# schematic.net
KiCad netlist of a schematic drawn in EasyEDA
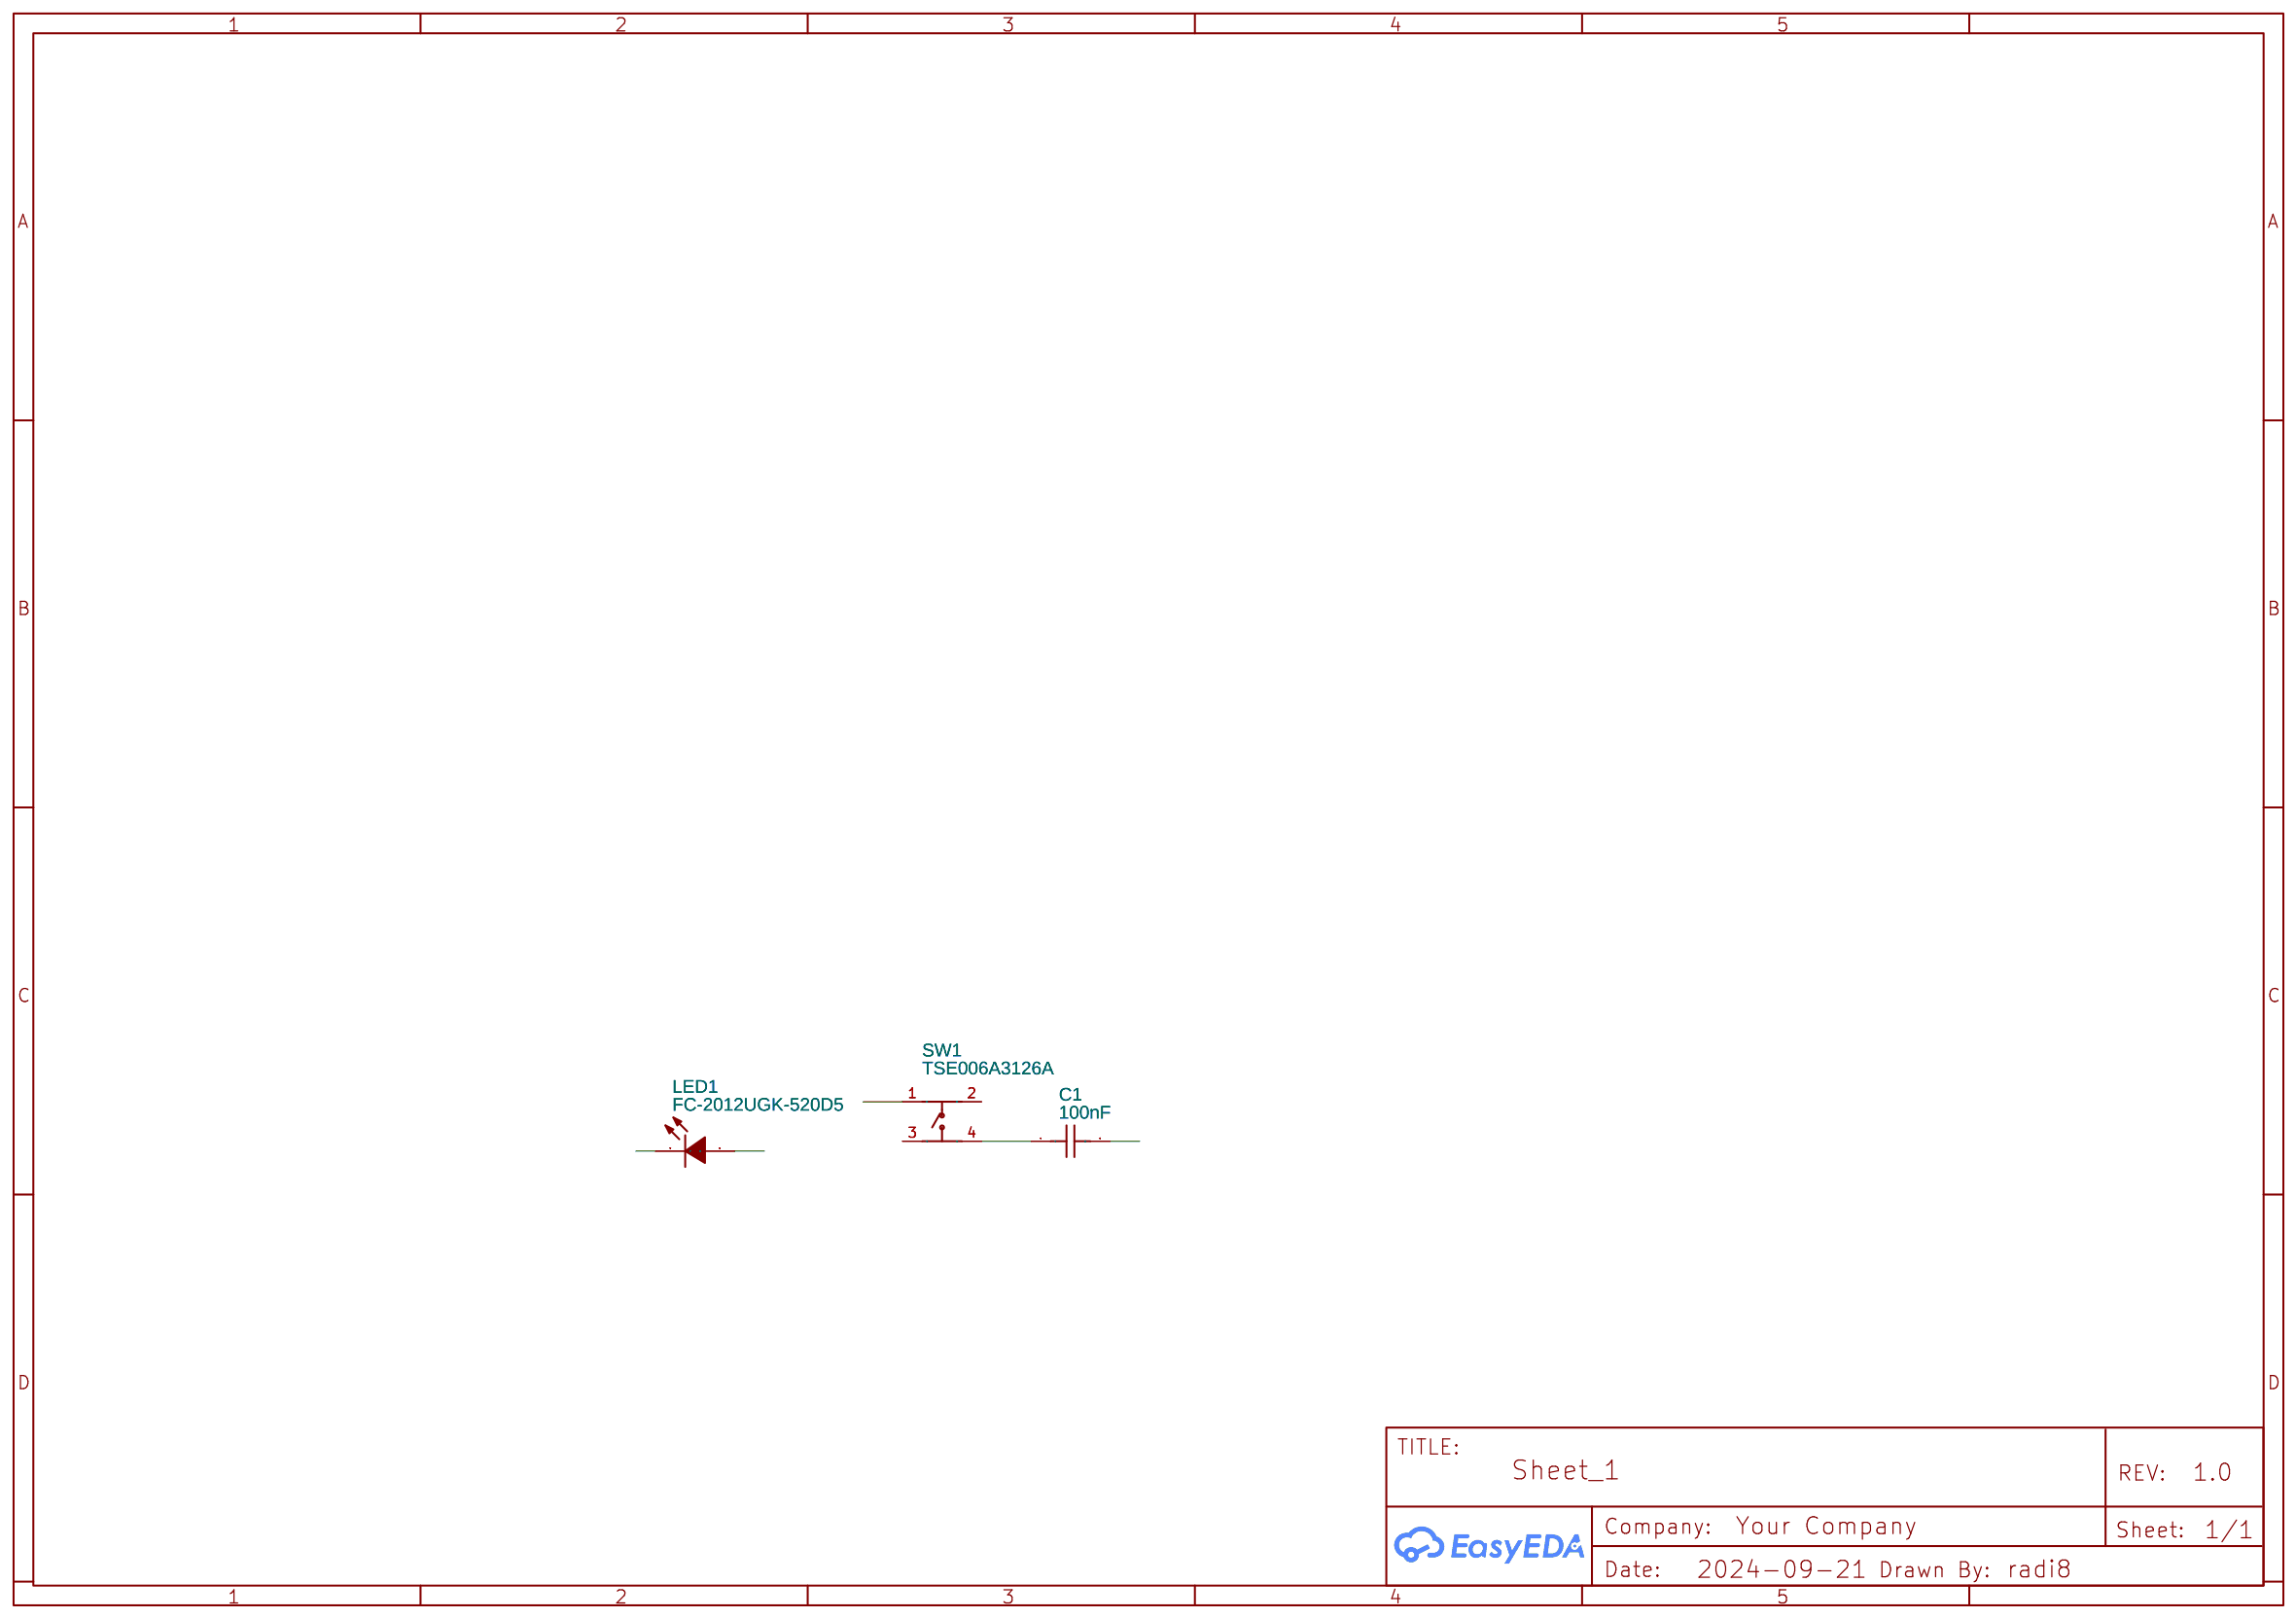
[diagram p0: schematic sheet]

(export (version "E")
  (design (tool "Eeschema 10.0.6"))
  (components
    (comp (ref "C1")
      (value "100nF")
      (fields
        (field (name "Manufacturer Part") "CL05B104KO5NNNC")
        (field (name "Manufacturer") "SAMSUNG(三星)")
      )
      (libsource (lib "") (part "CL05B104KO5NNNC"))
    )
    (comp (ref "LED1")
      (value "FC-2012UGK-520D5")
      (fields (field (name "Manufacturer Part") "NCD0805G1") (field (name "Manufacturer") "国星光电"))
      (libsource (lib "") (part "FC-2012UGK-520D5"))
    )
    (comp (ref "SW1")
      (value "TSE006A3126A")
      (fields (field (name "Manufacturer") "BZCN(博众电气)"))
      (libsource (lib "") (part "TSE006A3126A"))
    )
  )
  (nets
    (net (code "1") (name "Net-(C1-Pad1)") (class "Default")
      (node (ref "C1") (pin "1") (pinfunction "1_1") (pintype "unspecified"))
      (node (ref "SW1") (pin "4") (pinfunction "4_4") (pintype "unspecified"))
    )
    (net (code "2") (name "unconnected-(C1-Pad2)") (class "Default")
      (node (ref "C1") (pin "2") (pinfunction "2_2") (pintype "unspecified"))
    )
    (net (code "3") (name "unconnected-(LED1-A-Pad1)") (class "Default")
      (node (ref "LED1") (pin "1") (pinfunction "A_1") (pintype "unspecified"))
    )
    (net (code "4") (name "unconnected-(LED1-K-Pad2)") (class "Default")
      (node (ref "LED1") (pin "2") (pinfunction "K_2") (pintype "unspecified"))
    )
    (net (code "5") (name "unconnected-(SW1-Pad1)") (class "Default")
      (node (ref "SW1") (pin "1") (pinfunction "1_1") (pintype "unspecified"))
    )
    (net (code "6") (name "unconnected-(SW1-Pad2)") (class "Default")
      (node (ref "SW1") (pin "2") (pinfunction "2_2") (pintype "unspecified"))
    )
    (net (code "7") (name "unconnected-(SW1-Pad3)") (class "Default")
      (node (ref "SW1") (pin "3") (pinfunction "3_3") (pintype "unspecified"))
    )
  )
)
